# Inverter_V2_Reroute.net
KiCad netlist of a schematic drawn in EAGLE
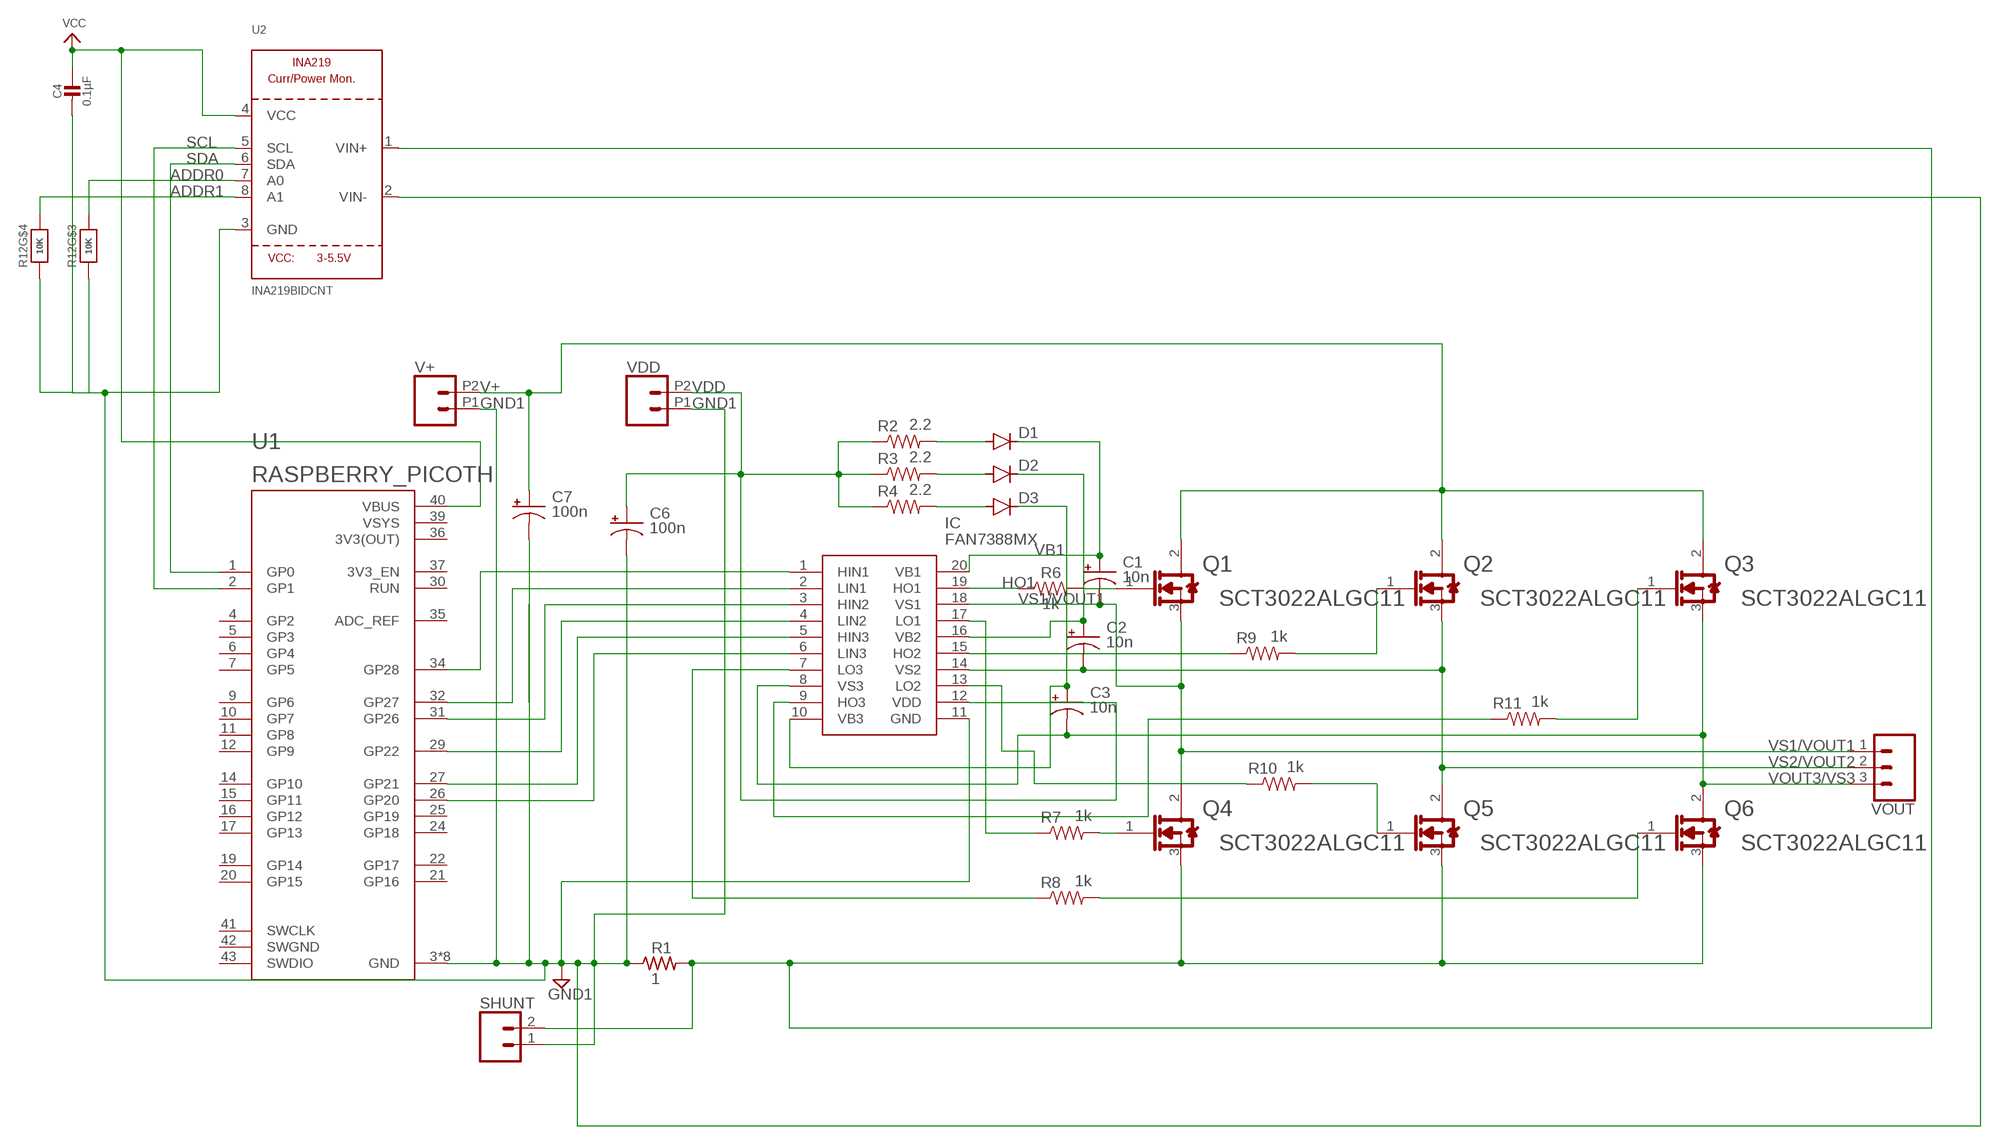
[diagram p0: schematic, sheet 1]

(export (version "E")
  (design (tool "Eeschema 10.0.6"))
  (components
    (comp (ref "C1")
      (value "10n")
      (footprint "eagle-import:SMC_Z")
      (libsource (lib "eagle-import") (part "CPOL-USSMCZ"))
    )
    (comp (ref "C2")
      (value "10n")
      (footprint "eagle-import:SMC_Z")
      (libsource (lib "eagle-import") (part "CPOL-USSMCZ"))
    )
    (comp (ref "C3")
      (value "10n")
      (footprint "eagle-import:SMC_Z")
      (libsource (lib "eagle-import") (part "CPOL-USSMCZ"))
    )
    (comp (ref "C4")
      (value "0.1µF")
      (footprint "eagle-import:0603-NO")
      (libsource (lib "eagle-import") (part "CAP_CERAMIC0603_NO"))
    )
    (comp (ref "C6")
      (value "100n")
      (footprint "eagle-import:SMC_Z")
      (libsource (lib "eagle-import") (part "CPOL-USSMCZ"))
    )
    (comp (ref "C7")
      (value "100n")
      (footprint "eagle-import:E5-5")
      (libsource (lib "eagle-import") (part "CPOL-USE5-5"))
    )
    (comp (ref "D1")
      (value "DIODE-GF1")
      (footprint "eagle-import:GF1")
      (libsource (lib "eagle-import") (part "DIODE-GF1"))
    )
    (comp (ref "D2")
      (value "DIODE-GF1")
      (footprint "eagle-import:GF1")
      (libsource (lib "eagle-import") (part "DIODE-GF1"))
    )
    (comp (ref "D3")
      (value "DIODE-GF1")
      (footprint "eagle-import:GF1")
      (libsource (lib "eagle-import") (part "DIODE-GF1"))
    )
    (comp (ref "IC")
      (value "FAN7388MX")
      (footprint "eagle-import:SOIC127P1032X265-20N")
      (fields (field (name "MOUSER_PART_NUMBER") "512-FAN7388MX"))
      (libsource (lib "eagle-import") (part "FAN7388MX"))
    )
    (comp (ref "Q1")
      (value "ROHM_SCT3022ALGC11ROHM_SCT3022ALGC11_0_0")
      (footprint "eagle-import:ROHM_SCT3022ALGC11_0")
      (fields
        (field (name "DIGIKEY_PART_NUMBER") "SCT3022ALGC11-ND")
        (field (name "MF") "ROHM")
        (field (name "MOUSER_PART_NUMBER") "755-SCT3022ALGC11")
      )
      (libsource (lib "eagle-import") (part "ROHM_SCT3022ALGC11ROHM_SCT3022ALGC11_0_0"))
    )
    (comp (ref "Q2")
      (value "ROHM_SCT3022ALGC11ROHM_SCT3022ALGC11_0_0")
      (footprint "eagle-import:ROHM_SCT3022ALGC11_0")
      (fields
        (field (name "DIGIKEY_PART_NUMBER") "SCT3022ALGC11-ND")
        (field (name "MF") "ROHM")
        (field (name "MOUSER_PART_NUMBER") "755-SCT3022ALGC11")
      )
      (libsource (lib "eagle-import") (part "ROHM_SCT3022ALGC11ROHM_SCT3022ALGC11_0_0"))
    )
    (comp (ref "Q3")
      (value "ROHM_SCT3022ALGC11ROHM_SCT3022ALGC11_0_0")
      (footprint "eagle-import:ROHM_SCT3022ALGC11_0")
      (fields
        (field (name "DIGIKEY_PART_NUMBER") "SCT3022ALGC11-ND")
        (field (name "MF") "ROHM")
        (field (name "MOUSER_PART_NUMBER") "755-SCT3022ALGC11")
      )
      (libsource (lib "eagle-import") (part "ROHM_SCT3022ALGC11ROHM_SCT3022ALGC11_0_0"))
    )
    (comp (ref "Q4")
      (value "ROHM_SCT3022ALGC11ROHM_SCT3022ALGC11_0_0")
      (footprint "eagle-import:ROHM_SCT3022ALGC11_0")
      (fields
        (field (name "DIGIKEY_PART_NUMBER") "SCT3022ALGC11-ND")
        (field (name "MF") "ROHM")
        (field (name "MOUSER_PART_NUMBER") "755-SCT3022ALGC11")
      )
      (libsource (lib "eagle-import") (part "ROHM_SCT3022ALGC11ROHM_SCT3022ALGC11_0_0"))
    )
    (comp (ref "Q5")
      (value "ROHM_SCT3022ALGC11ROHM_SCT3022ALGC11_0_0")
      (footprint "eagle-import:ROHM_SCT3022ALGC11_0")
      (fields
        (field (name "DIGIKEY_PART_NUMBER") "SCT3022ALGC11-ND")
        (field (name "MF") "ROHM")
        (field (name "MOUSER_PART_NUMBER") "755-SCT3022ALGC11")
      )
      (libsource (lib "eagle-import") (part "ROHM_SCT3022ALGC11ROHM_SCT3022ALGC11_0_0"))
    )
    (comp (ref "Q6")
      (value "ROHM_SCT3022ALGC11ROHM_SCT3022ALGC11_0_0")
      (footprint "eagle-import:ROHM_SCT3022ALGC11_0")
      (fields
        (field (name "DIGIKEY_PART_NUMBER") "SCT3022ALGC11-ND")
        (field (name "MF") "ROHM")
        (field (name "MOUSER_PART_NUMBER") "755-SCT3022ALGC11")
      )
      (libsource (lib "eagle-import") (part "ROHM_SCT3022ALGC11ROHM_SCT3022ALGC11_0_0"))
    )
    (comp (ref "R1")
      (value "1")
      (footprint "eagle-import:0207_10")
      (libsource (lib "eagle-import") (part "R-US_0207/10"))
    )
    (comp (ref "R2")
      (value "2.2")
      (footprint "eagle-import:0603")
      (libsource (lib "eagle-import") (part "RESISTOR0603"))
    )
    (comp (ref "R3")
      (value "2.2")
      (footprint "eagle-import:0603")
      (libsource (lib "eagle-import") (part "RESISTOR0603"))
    )
    (comp (ref "R4")
      (value "2.2")
      (footprint "eagle-import:0603")
      (libsource (lib "eagle-import") (part "RESISTOR0603"))
    )
    (comp (ref "R6")
      (value "1k")
      (footprint "eagle-import:0603")
      (libsource (lib "eagle-import") (part "RESISTOR0603"))
    )
    (comp (ref "R7")
      (value "1k")
      (footprint "eagle-import:0603")
      (libsource (lib "eagle-import") (part "RESISTOR0603"))
    )
    (comp (ref "R8")
      (value "1k")
      (footprint "eagle-import:0603")
      (libsource (lib "eagle-import") (part "RESISTOR0603"))
    )
    (comp (ref "R9")
      (value "1k")
      (footprint "eagle-import:0603")
      (libsource (lib "eagle-import") (part "RESISTOR0603"))
    )
    (comp (ref "R10")
      (value "1k")
      (footprint "eagle-import:0603")
      (libsource (lib "eagle-import") (part "RESISTOR0603"))
    )
    (comp (ref "R11")
      (value "1k")
      (footprint "eagle-import:0603")
      (libsource (lib "eagle-import") (part "RESISTOR0603"))
    )
    (comp (ref "R12")
      (value "10K")
      (footprint "eagle-import:RESPACK_4X0603")
      (libsource (lib "eagle-import") (part "RESISTOR_4PACK"))
    )
    (comp (ref "SHUNT")
      (value "CONN_02PTH4")
      (footprint "eagle-import:1X02_XTRA_BIG")
      (libsource (lib "eagle-import") (part "CONN_02PTH4"))
    )
    (comp (ref "U1")
      (value "RASPBERRY_PICOTH")
      (footprint "eagle-import:PICO-PKG-TH")
      (libsource (lib "eagle-import") (part "RASPBERRY_PICOTH"))
    )
    (comp (ref "U2")
      (value "INA219BIDCNT")
      (footprint "eagle-import:SOT23-8")
      (libsource (lib "eagle-import") (part "INA219"))
    )
    (comp (ref "V+")
      (value "CONN_022.54MM_SCREWTERM")
      (footprint "eagle-import:1X02_2.54_SCREWTERM")
      (libsource (lib "eagle-import") (part "CONN_022.54MM_SCREWTERM"))
    )
    (comp (ref "VDD")
      (value "CONN_022.54MM_SCREWTERM")
      (footprint "eagle-import:1X02_2.54_SCREWTERM")
      (libsource (lib "eagle-import") (part "CONN_022.54MM_SCREWTERM"))
    )
    (comp (ref "VOUT")
      (value "CONN_03SCREW-NS")
      (footprint "eagle-import:SCREWTERMINAL-3.5MM-3-NS")
      (libsource (lib "eagle-import") (part "CONN_03SCREW-NS"))
    )
  )
  (nets
    (net (code "1") (name "/3V3(OUT)") (class "Default")
      (node (ref "U1") (pin "36") (pinfunction "3V3(OUT)_36") (pintype "power_in"))
    )
    (net (code "2") (name "/ADDR0") (class "Default")
      (node (ref "R12") (pin "6") (pinfunction "2_6") (pintype "passive"))
      (node (ref "U2") (pin "7") (pinfunction "A0_7") (pintype "bidirectional"))
    )
    (net (code "3") (name "/ADDR1") (class "Default")
      (node (ref "R12") (pin "5") (pinfunction "2_5") (pintype "passive"))
      (node (ref "U2") (pin "8") (pinfunction "A1_8") (pintype "bidirectional"))
    )
    (net (code "4") (name "/HO1") (class "Default")
      (node (ref "IC") (pin "19") (pinfunction "HO1_19") (pintype "bidirectional"))
      (node (ref "R6") (pin "1") (pinfunction "1_1") (pintype "passive"))
    )
    (net (code "5") (name "/SCL") (class "Default")
      (node (ref "U1") (pin "2") (pinfunction "GP1_2") (pintype "bidirectional"))
      (node (ref "U2") (pin "5") (pinfunction "SCL_5") (pintype "bidirectional"))
    )
    (net (code "6") (name "/SDA") (class "Default")
      (node (ref "U1") (pin "1") (pinfunction "GP0_1") (pintype "bidirectional"))
      (node (ref "U2") (pin "6") (pinfunction "SDA_6") (pintype "bidirectional"))
    )
    (net (code "7") (name "/SWGND") (class "Default")
      (node (ref "U1") (pin "42") (pinfunction "SWGND_42") (pintype "power_in"))
    )
    (net (code "8") (name "/V+") (class "Default")
      (node (ref "C7") (pin "+") (pinfunction "+_+") (pintype "passive"))
      (node (ref "Q1") (pin "2") (pinfunction "DRAIN_2") (pintype "passive"))
      (node (ref "Q2") (pin "2") (pinfunction "DRAIN_2") (pintype "passive"))
      (node (ref "Q3") (pin "2") (pinfunction "DRAIN_2") (pintype "passive"))
      (node (ref "V+") (pin "P2") (pinfunction "2_P2") (pintype "passive"))
    )
    (net (code "9") (name "/VB1") (class "Default")
      (node (ref "C1") (pin "+") (pinfunction "+_+") (pintype "passive"))
      (node (ref "D1") (pin "C") (pinfunction "C_C") (pintype "passive"))
      (node (ref "IC") (pin "20") (pinfunction "VB1_20") (pintype "bidirectional"))
    )
    (net (code "10") (name "/VDD") (class "Default")
      (node (ref "C6") (pin "+") (pinfunction "+_+") (pintype "passive"))
      (node (ref "IC") (pin "12") (pinfunction "VDD_12") (pintype "bidirectional"))
      (node (ref "R2") (pin "1") (pinfunction "1_1") (pintype "passive"))
      (node (ref "R3") (pin "1") (pinfunction "1_1") (pintype "passive"))
      (node (ref "R4") (pin "1") (pinfunction "1_1") (pintype "passive"))
      (node (ref "VDD") (pin "P2") (pinfunction "2_P2") (pintype "passive"))
    )
    (net (code "11") (name "/VOUT3{slash}VS3") (class "Default")
      (node (ref "C3") (pin "-") (pinfunction "-_-") (pintype "passive"))
      (node (ref "IC") (pin "8") (pinfunction "VS3_8") (pintype "bidirectional"))
      (node (ref "Q3") (pin "3") (pinfunction "SOURCE_3") (pintype "passive"))
      (node (ref "Q6") (pin "2") (pinfunction "DRAIN_2") (pintype "passive"))
      (node (ref "VOUT") (pin "3") (pinfunction "3_3") (pintype "passive"))
    )
    (net (code "12") (name "/VS1{slash}VOUT1") (class "Default")
      (node (ref "C1") (pin "-") (pinfunction "-_-") (pintype "passive"))
      (node (ref "IC") (pin "18") (pinfunction "VS1_18") (pintype "bidirectional"))
      (node (ref "Q1") (pin "3") (pinfunction "SOURCE_3") (pintype "passive"))
      (node (ref "Q4") (pin "2") (pinfunction "DRAIN_2") (pintype "passive"))
      (node (ref "VOUT") (pin "1") (pinfunction "1_1") (pintype "passive"))
    )
    (net (code "13") (name "/VS2{slash}VOUT2") (class "Default")
      (node (ref "C2") (pin "-") (pinfunction "-_-") (pintype "passive"))
      (node (ref "IC") (pin "14") (pinfunction "VS2_14") (pintype "bidirectional"))
      (node (ref "Q2") (pin "3") (pinfunction "SOURCE_3") (pintype "passive"))
      (node (ref "Q5") (pin "2") (pinfunction "DRAIN_2") (pintype "passive"))
      (node (ref "VOUT") (pin "2") (pinfunction "2_2") (pintype "passive"))
    )
    (net (code "14") (name "/VSYS") (class "Default")
      (node (ref "U1") (pin "39") (pinfunction "VSYS_39") (pintype "power_in"))
    )
    (net (code "15") (name "GND1") (class "Default")
      (node (ref "C4") (pin "2") (pinfunction "2_2") (pintype "passive"))
      (node (ref "C6") (pin "-") (pinfunction "-_-") (pintype "passive"))
      (node (ref "C7") (pin "-") (pinfunction "-_-") (pintype "passive"))
      (node (ref "IC") (pin "11") (pinfunction "GND_11") (pintype "bidirectional"))
      (node (ref "R1") (pin "1") (pinfunction "1_1") (pintype "passive"))
      (node (ref "R12") (pin "3") (pinfunction "1_3") (pintype "passive"))
      (node (ref "R12") (pin "4") (pinfunction "1_4") (pintype "passive"))
      (node (ref "SHUNT") (pin "1") (pinfunction "1_1") (pintype "passive"))
      (node (ref "U1") (pin "13") (pinfunction "GND_13") (pintype "power_in"))
      (node (ref "U1") (pin "18") (pinfunction "GND_18") (pintype "power_in"))
      (node (ref "U1") (pin "23") (pinfunction "GND_23") (pintype "power_in"))
      (node (ref "U1") (pin "28") (pinfunction "GND_28") (pintype "power_in"))
      (node (ref "U1") (pin "3") (pinfunction "GND_3") (pintype "power_in"))
      (node (ref "U1") (pin "33") (pinfunction "GND_33") (pintype "power_in"))
      (node (ref "U1") (pin "38") (pinfunction "GND_38") (pintype "power_in"))
      (node (ref "U1") (pin "8") (pinfunction "GND_8") (pintype "power_in"))
      (node (ref "U2") (pin "2") (pinfunction "VIN-_2") (pintype "bidirectional"))
      (node (ref "U2") (pin "3") (pinfunction "GND_3") (pintype "power_in"))
      (node (ref "V+") (pin "P1") (pinfunction "1_P1") (pintype "passive"))
      (node (ref "VDD") (pin "P1") (pinfunction "1_P1") (pintype "passive"))
    )
    (net (code "16") (name "Net-(D1-PadA)") (class "Default")
      (node (ref "D1") (pin "A") (pinfunction "A_A") (pintype "passive"))
      (node (ref "R2") (pin "2") (pinfunction "2_2") (pintype "passive"))
    )
    (net (code "17") (name "Net-(D2-PadA)") (class "Default")
      (node (ref "D2") (pin "A") (pinfunction "A_A") (pintype "passive"))
      (node (ref "R3") (pin "2") (pinfunction "2_2") (pintype "passive"))
    )
    (net (code "18") (name "Net-(D3-PadA)") (class "Default")
      (node (ref "D3") (pin "A") (pinfunction "A_A") (pintype "passive"))
      (node (ref "R4") (pin "2") (pinfunction "2_2") (pintype "passive"))
    )
    (net (code "19") (name "Net-(IC-HIN1)") (class "Default")
      (node (ref "IC") (pin "1") (pinfunction "HIN1_1") (pintype "bidirectional"))
      (node (ref "U1") (pin "34") (pinfunction "GP28_34") (pintype "bidirectional"))
    )
    (net (code "20") (name "Net-(IC-HIN2)") (class "Default")
      (node (ref "IC") (pin "3") (pinfunction "HIN2_3") (pintype "bidirectional"))
      (node (ref "U1") (pin "31") (pinfunction "GP26_31") (pintype "bidirectional"))
    )
    (net (code "21") (name "Net-(IC-HIN3)") (class "Default")
      (node (ref "IC") (pin "5") (pinfunction "HIN3_5") (pintype "bidirectional"))
      (node (ref "U1") (pin "27") (pinfunction "GP21_27") (pintype "bidirectional"))
    )
    (net (code "22") (name "Net-(IC-HO2)") (class "Default")
      (node (ref "IC") (pin "15") (pinfunction "HO2_15") (pintype "bidirectional"))
      (node (ref "R9") (pin "1") (pinfunction "1_1") (pintype "passive"))
    )
    (net (code "23") (name "Net-(IC-HO3)") (class "Default")
      (node (ref "IC") (pin "9") (pinfunction "HO3_9") (pintype "bidirectional"))
      (node (ref "R11") (pin "1") (pinfunction "1_1") (pintype "passive"))
    )
    (net (code "24") (name "Net-(IC-LIN1)") (class "Default")
      (node (ref "IC") (pin "2") (pinfunction "LIN1_2") (pintype "bidirectional"))
      (node (ref "U1") (pin "32") (pinfunction "GP27_32") (pintype "bidirectional"))
    )
    (net (code "25") (name "Net-(IC-LIN2)") (class "Default")
      (node (ref "IC") (pin "4") (pinfunction "LIN2_4") (pintype "bidirectional"))
      (node (ref "U1") (pin "29") (pinfunction "GP22_29") (pintype "bidirectional"))
    )
    (net (code "26") (name "Net-(IC-LIN3)") (class "Default")
      (node (ref "IC") (pin "6") (pinfunction "LIN3_6") (pintype "bidirectional"))
      (node (ref "U1") (pin "26") (pinfunction "GP20_26") (pintype "bidirectional"))
    )
    (net (code "27") (name "Net-(IC-LO1)") (class "Default")
      (node (ref "IC") (pin "17") (pinfunction "LO1_17") (pintype "bidirectional"))
      (node (ref "R7") (pin "1") (pinfunction "1_1") (pintype "passive"))
    )
    (net (code "28") (name "Net-(IC-LO2)") (class "Default")
      (node (ref "IC") (pin "13") (pinfunction "LO2_13") (pintype "bidirectional"))
      (node (ref "R10") (pin "1") (pinfunction "1_1") (pintype "passive"))
    )
    (net (code "29") (name "Net-(IC-LO3)") (class "Default")
      (node (ref "IC") (pin "7") (pinfunction "LO3_7") (pintype "bidirectional"))
      (node (ref "R8") (pin "1") (pinfunction "1_1") (pintype "passive"))
    )
    (net (code "30") (name "Net-(IC-VB2)") (class "Default")
      (node (ref "C2") (pin "+") (pinfunction "+_+") (pintype "passive"))
      (node (ref "D2") (pin "C") (pinfunction "C_C") (pintype "passive"))
      (node (ref "IC") (pin "16") (pinfunction "VB2_16") (pintype "bidirectional"))
    )
    (net (code "31") (name "Net-(IC-VB3)") (class "Default")
      (node (ref "C3") (pin "+") (pinfunction "+_+") (pintype "passive"))
      (node (ref "D3") (pin "C") (pinfunction "C_C") (pintype "passive"))
      (node (ref "IC") (pin "10") (pinfunction "VB3_10") (pintype "bidirectional"))
    )
    (net (code "32") (name "Net-(Q1-GATE)") (class "Default")
      (node (ref "Q1") (pin "1") (pinfunction "GATE_1") (pintype "passive"))
      (node (ref "R6") (pin "2") (pinfunction "2_2") (pintype "passive"))
    )
    (net (code "33") (name "Net-(Q2-GATE)") (class "Default")
      (node (ref "Q2") (pin "1") (pinfunction "GATE_1") (pintype "passive"))
      (node (ref "R9") (pin "2") (pinfunction "2_2") (pintype "passive"))
    )
    (net (code "34") (name "Net-(Q3-GATE)") (class "Default")
      (node (ref "Q3") (pin "1") (pinfunction "GATE_1") (pintype "passive"))
      (node (ref "R11") (pin "2") (pinfunction "2_2") (pintype "passive"))
    )
    (net (code "35") (name "Net-(Q4-GATE)") (class "Default")
      (node (ref "Q4") (pin "1") (pinfunction "GATE_1") (pintype "passive"))
      (node (ref "R7") (pin "2") (pinfunction "2_2") (pintype "passive"))
    )
    (net (code "36") (name "Net-(Q4-SOURCE)") (class "Default")
      (node (ref "Q4") (pin "3") (pinfunction "SOURCE_3") (pintype "passive"))
      (node (ref "Q5") (pin "3") (pinfunction "SOURCE_3") (pintype "passive"))
      (node (ref "Q6") (pin "3") (pinfunction "SOURCE_3") (pintype "passive"))
      (node (ref "R1") (pin "2") (pinfunction "2_2") (pintype "passive"))
      (node (ref "SHUNT") (pin "2") (pinfunction "2_2") (pintype "passive"))
      (node (ref "U2") (pin "1") (pinfunction "VIN+_1") (pintype "bidirectional"))
    )
    (net (code "37") (name "Net-(Q5-GATE)") (class "Default")
      (node (ref "Q5") (pin "1") (pinfunction "GATE_1") (pintype "passive"))
      (node (ref "R10") (pin "2") (pinfunction "2_2") (pintype "passive"))
    )
    (net (code "38") (name "Net-(Q6-GATE)") (class "Default")
      (node (ref "Q6") (pin "1") (pinfunction "GATE_1") (pintype "passive"))
      (node (ref "R8") (pin "2") (pinfunction "2_2") (pintype "passive"))
    )
    (net (code "39") (name "VCC") (class "Default")
      (node (ref "C4") (pin "1") (pinfunction "1_1") (pintype "passive"))
      (node (ref "U1") (pin "40") (pinfunction "VBUS_40") (pintype "power_in"))
      (node (ref "U2") (pin "4") (pinfunction "VCC_4") (pintype "power_in"))
    )
    (net (code "40") (name "unconnected-(U1-3V3_EN-Pad37)") (class "Default")
      (node (ref "U1") (pin "37") (pinfunction "3V3_EN_37") (pintype "input"))
    )
    (net (code "41") (name "unconnected-(U1-ADC_REF-Pad35)") (class "Default")
      (node (ref "U1") (pin "35") (pinfunction "ADC_REF_35") (pintype "input"))
    )
    (net (code "42") (name "unconnected-(U1-GP2-Pad4)") (class "Default")
      (node (ref "U1") (pin "4") (pinfunction "GP2_4") (pintype "bidirectional"))
    )
    (net (code "43") (name "unconnected-(U1-GP3-Pad5)") (class "Default")
      (node (ref "U1") (pin "5") (pinfunction "GP3_5") (pintype "bidirectional"))
    )
    (net (code "44") (name "unconnected-(U1-GP4-Pad6)") (class "Default")
      (node (ref "U1") (pin "6") (pinfunction "GP4_6") (pintype "bidirectional"))
    )
    (net (code "45") (name "unconnected-(U1-GP5-Pad7)") (class "Default")
      (node (ref "U1") (pin "7") (pinfunction "GP5_7") (pintype "bidirectional"))
    )
    (net (code "46") (name "unconnected-(U1-GP6-Pad9)") (class "Default")
      (node (ref "U1") (pin "9") (pinfunction "GP6_9") (pintype "bidirectional"))
    )
    (net (code "47") (name "unconnected-(U1-GP7-Pad10)") (class "Default")
      (node (ref "U1") (pin "10") (pinfunction "GP7_10") (pintype "bidirectional"))
    )
    (net (code "48") (name "unconnected-(U1-GP8-Pad11)") (class "Default")
      (node (ref "U1") (pin "11") (pinfunction "GP8_11") (pintype "bidirectional"))
    )
    (net (code "49") (name "unconnected-(U1-GP9-Pad12)") (class "Default")
      (node (ref "U1") (pin "12") (pinfunction "GP9_12") (pintype "bidirectional"))
    )
    (net (code "50") (name "unconnected-(U1-GP10-Pad14)") (class "Default")
      (node (ref "U1") (pin "14") (pinfunction "GP10_14") (pintype "bidirectional"))
    )
    (net (code "51") (name "unconnected-(U1-GP11-Pad15)") (class "Default")
      (node (ref "U1") (pin "15") (pinfunction "GP11_15") (pintype "bidirectional"))
    )
    (net (code "52") (name "unconnected-(U1-GP12-Pad16)") (class "Default")
      (node (ref "U1") (pin "16") (pinfunction "GP12_16") (pintype "bidirectional"))
    )
    (net (code "53") (name "unconnected-(U1-GP13-Pad17)") (class "Default")
      (node (ref "U1") (pin "17") (pinfunction "GP13_17") (pintype "bidirectional"))
    )
    (net (code "54") (name "unconnected-(U1-GP14-Pad19)") (class "Default")
      (node (ref "U1") (pin "19") (pinfunction "GP14_19") (pintype "bidirectional"))
    )
    (net (code "55") (name "unconnected-(U1-GP15-Pad20)") (class "Default")
      (node (ref "U1") (pin "20") (pinfunction "GP15_20") (pintype "bidirectional"))
    )
    (net (code "56") (name "unconnected-(U1-GP16-Pad21)") (class "Default")
      (node (ref "U1") (pin "21") (pinfunction "GP16_21") (pintype "bidirectional"))
    )
    (net (code "57") (name "unconnected-(U1-GP17-Pad22)") (class "Default")
      (node (ref "U1") (pin "22") (pinfunction "GP17_22") (pintype "bidirectional"))
    )
    (net (code "58") (name "unconnected-(U1-GP18-Pad24)") (class "Default")
      (node (ref "U1") (pin "24") (pinfunction "GP18_24") (pintype "bidirectional"))
    )
    (net (code "59") (name "unconnected-(U1-GP19-Pad25)") (class "Default")
      (node (ref "U1") (pin "25") (pinfunction "GP19_25") (pintype "bidirectional"))
    )
    (net (code "60") (name "unconnected-(U1-RUN-Pad30)") (class "Default")
      (node (ref "U1") (pin "30") (pinfunction "RUN_30") (pintype "input"))
    )
    (net (code "61") (name "unconnected-(U1-SWCLK-Pad41)") (class "Default")
      (node (ref "U1") (pin "41") (pinfunction "SWCLK_41") (pintype "input"))
    )
    (net (code "62") (name "unconnected-(U1-SWDIO-Pad43)") (class "Default")
      (node (ref "U1") (pin "43") (pinfunction "SWDIO_43") (pintype "bidirectional"))
    )
  )
)
